# arm.net
KiCad netlist of a schematic drawn in Altium Designer
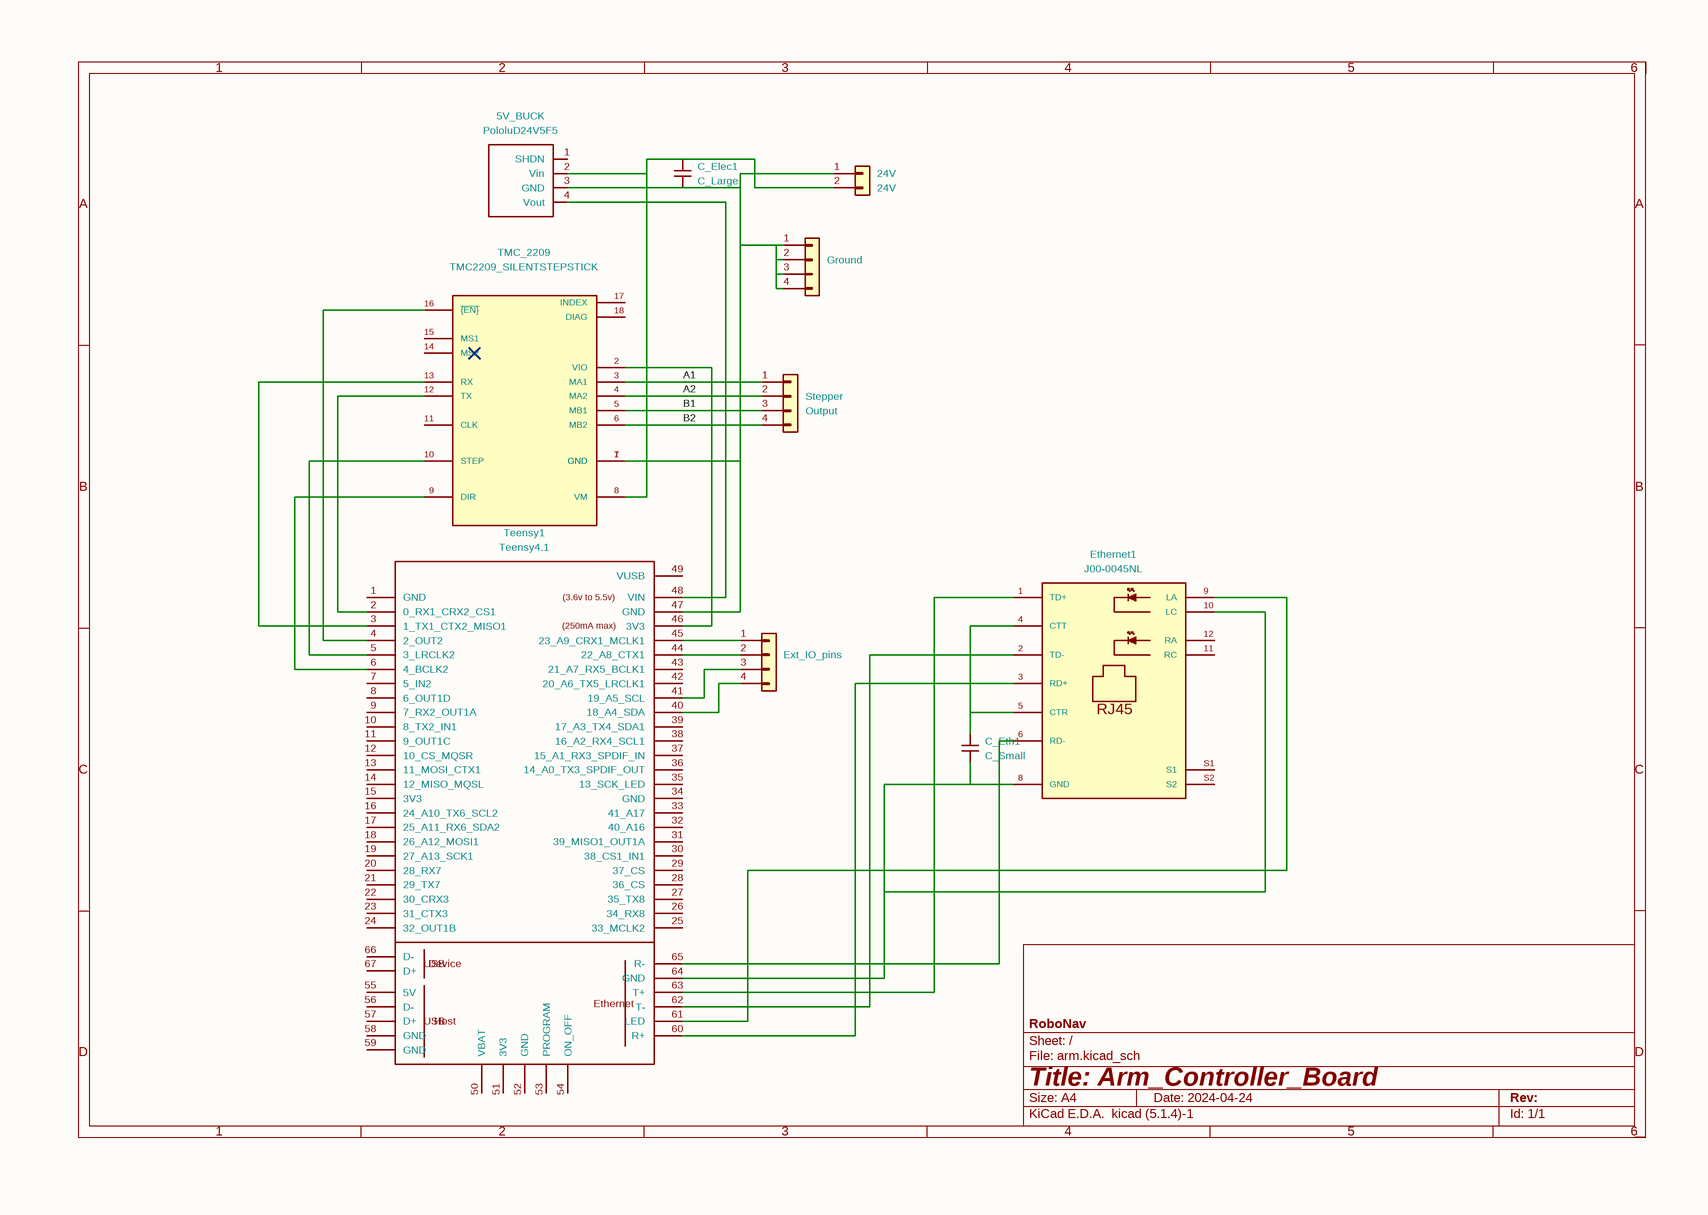
[diagram p0: arm.SchDoc]

(export (version "E")
  (design (tool "Eeschema 10.0.6"))
  (components
    (comp (ref "5V_BUCK") (value "PololuD24V5F5") (libsource (lib "Pololu_5V_D24V5F5") (part "D24V5F5")))
    (comp (ref "24V") (value "24V") (libsource (lib "Connector_Generic") (part "Conn_01x02")))
    (comp (ref "C_Elec1")
      (value "C_Large")
      (description "Unpolarized capacitor, small symbol")
      (libsource (lib "Device") (part "C_Small"))
    )
    (comp (ref "C_Eth1")
      (value "C_Small")
      (description "Unpolarized capacitor, small symbol")
      (libsource (lib "Device") (part "C_Small"))
    )
    (comp (ref "Ethernet1")
      (value "J00-0045NL")
      (description "Conn RJ-45 Integrated Magnetics F 8 POS 2.54mm Solder RA Thru-Hole 12 Terminal 1 Port Cat 5/Cat 6")
      (fields (field (name "MF") "Pulse Electronics"))
      (libsource (lib "EthernetHead") (part "J00-0045NL"))
    )
    (comp (ref "Ext_IO_pins") (value "Output") (libsource (lib "Connector_Generic") (part "Conn_01x04")))
    (comp (ref "Ground") (value "Output") (libsource (lib "Connector_Generic") (part "Conn_01x04")))
    (comp (ref "Stepper") (value "Output") (libsource (lib "Connector_Generic") (part "Conn_01x04")))
    (comp (ref "Teensy1") (value "Teensy4.1") (libsource (lib "Teensy") (part "Teensy4.1")))
    (comp (ref "TMC_2209")
      (value "TMC2209_SILENTSTEPSTICK")
      (libsource (lib "TMC2209_SILENTSTEPSTICK") (part "TMC2209_SILENTSTEPSTICK"))
    )
  )
  (nets
    (net (code "1") (name "/A1") (class "Default")
      (node (ref "Stepper") (pin "1") (pinfunction "Pin_1_1") (pintype "passive"))
      (node (ref "TMC_2209") (pin "3") (pinfunction "MA1_3") (pintype "passive"))
    )
    (net (code "2") (name "/A2") (class "Default")
      (node (ref "Stepper") (pin "2") (pinfunction "Pin_2_2") (pintype "passive"))
      (node (ref "TMC_2209") (pin "4") (pinfunction "MA2_4") (pintype "passive"))
    )
    (net (code "3") (name "/B1") (class "Default")
      (node (ref "Stepper") (pin "3") (pinfunction "Pin_3_3") (pintype "passive"))
      (node (ref "TMC_2209") (pin "5") (pinfunction "MB1_5") (pintype "passive"))
    )
    (net (code "4") (name "/B2") (class "Default")
      (node (ref "Stepper") (pin "4") (pinfunction "Pin_4_4") (pintype "passive"))
      (node (ref "TMC_2209") (pin "6") (pinfunction "MB2_6") (pintype "passive"))
    )
    (net (code "5") (name "Net-(5V_BUCK-Vout)") (class "Default")
      (node (ref "5V_BUCK") (pin "4") (pinfunction "Vout_4") (pintype "passive"))
      (node (ref "Teensy1") (pin "48") (pinfunction "VIN_48") (pintype "passive"))
    )
    (net (code "6") (name "Net-(24V-Pin_1)") (class "Default")
      (node (ref "24V") (pin "1") (pinfunction "Pin_1_1") (pintype "passive"))
      (node (ref "5V_BUCK") (pin "3") (pinfunction "GND_3") (pintype "passive"))
      (node (ref "C_Elec1") (pin "2") (pinfunction "2_2") (pintype "passive"))
      (node (ref "Ground") (pin "1") (pinfunction "Pin_1_1") (pintype "passive"))
      (node (ref "Ground") (pin "2") (pinfunction "Pin_2_2") (pintype "passive"))
      (node (ref "Ground") (pin "3") (pinfunction "Pin_3_3") (pintype "passive"))
      (node (ref "Ground") (pin "4") (pinfunction "Pin_4_4") (pintype "passive"))
      (node (ref "TMC_2209") (pin "1") (pinfunction "GND_1") (pintype "passive"))
      (node (ref "TMC_2209") (pin "7") (pinfunction "GND_7") (pintype "passive"))
      (node (ref "Teensy1") (pin "47") (pinfunction "GND_47") (pintype "passive"))
    )
    (net (code "7") (name "Net-(24V-Pin_2)") (class "Default")
      (node (ref "24V") (pin "2") (pinfunction "Pin_2_2") (pintype "passive"))
      (node (ref "5V_BUCK") (pin "2") (pinfunction "Vin_2") (pintype "passive"))
      (node (ref "C_Elec1") (pin "1") (pinfunction "1_1") (pintype "passive"))
      (node (ref "TMC_2209") (pin "8") (pinfunction "VM_8") (pintype "passive"))
    )
    (net (code "8") (name "Net-(Ethernet1-CTR)") (class "Default")
      (node (ref "C_Eth1") (pin "1") (pinfunction "1_1") (pintype "passive"))
      (node (ref "Ethernet1") (pin "4") (pinfunction "CTT_4") (pintype "passive"))
      (node (ref "Ethernet1") (pin "5") (pinfunction "CTR_5") (pintype "passive"))
    )
    (net (code "9") (name "Net-(Ethernet1-GND)") (class "Default")
      (node (ref "C_Eth1") (pin "2") (pinfunction "2_2") (pintype "passive"))
      (node (ref "Ethernet1") (pin "10") (pinfunction "LC_10") (pintype "passive"))
      (node (ref "Ethernet1") (pin "8") (pinfunction "GND_8") (pintype "passive"))
      (node (ref "Teensy1") (pin "64") (pinfunction "GND_64") (pintype "passive"))
    )
    (net (code "10") (name "Net-(Ethernet1-LA)") (class "Default")
      (node (ref "Ethernet1") (pin "9") (pinfunction "LA_9") (pintype "passive"))
      (node (ref "Teensy1") (pin "61") (pinfunction "LED_61") (pintype "passive"))
    )
    (net (code "11") (name "Net-(Ethernet1-RD+)") (class "Default")
      (node (ref "Ethernet1") (pin "3") (pinfunction "RD+_3") (pintype "passive"))
      (node (ref "Teensy1") (pin "60") (pinfunction "R+_60") (pintype "passive"))
    )
    (net (code "12") (name "Net-(Ethernet1-RD-)") (class "Default")
      (node (ref "Ethernet1") (pin "6") (pinfunction "RD-_6") (pintype "passive"))
      (node (ref "Teensy1") (pin "65") (pinfunction "R-_65") (pintype "passive"))
    )
    (net (code "13") (name "Net-(Ethernet1-TD+)") (class "Default")
      (node (ref "Ethernet1") (pin "1") (pinfunction "TD+_1") (pintype "passive"))
      (node (ref "Teensy1") (pin "63") (pinfunction "T+_63") (pintype "passive"))
    )
    (net (code "14") (name "Net-(Ethernet1-TD-)") (class "Default")
      (node (ref "Ethernet1") (pin "2") (pinfunction "TD-_2") (pintype "passive"))
      (node (ref "Teensy1") (pin "62") (pinfunction "T-_62") (pintype "passive"))
    )
    (net (code "15") (name "Net-(Ext_IO_pins-Pin_1)") (class "Default")
      (node (ref "Ext_IO_pins") (pin "1") (pinfunction "Pin_1_1") (pintype "passive"))
      (node (ref "Teensy1") (pin "45") (pinfunction "23_A9_CRX1_MCLK1_45") (pintype "passive"))
    )
    (net (code "16") (name "Net-(Ext_IO_pins-Pin_2)") (class "Default")
      (node (ref "Ext_IO_pins") (pin "2") (pinfunction "Pin_2_2") (pintype "passive"))
      (node (ref "Teensy1") (pin "44") (pinfunction "22_A8_CTX1_44") (pintype "passive"))
    )
    (net (code "17") (name "Net-(Ext_IO_pins-Pin_3)") (class "Default")
      (node (ref "Ext_IO_pins") (pin "3") (pinfunction "Pin_3_3") (pintype "passive"))
      (node (ref "Teensy1") (pin "41") (pinfunction "19_A5_SCL_41") (pintype "passive"))
    )
    (net (code "18") (name "Net-(Ext_IO_pins-Pin_4)") (class "Default")
      (node (ref "Ext_IO_pins") (pin "4") (pinfunction "Pin_4_4") (pintype "passive"))
      (node (ref "Teensy1") (pin "40") (pinfunction "18_A4_SDA_40") (pintype "passive"))
    )
    (net (code "19") (name "Net-(TMC_2209-DIR)") (class "Default")
      (node (ref "TMC_2209") (pin "9") (pinfunction "DIR_9") (pintype "passive"))
      (node (ref "Teensy1") (pin "6") (pinfunction "4_BCLK2_6") (pintype "passive"))
    )
    (net (code "20") (name "Net-(TMC_2209-RX)") (class "Default")
      (node (ref "TMC_2209") (pin "13") (pinfunction "RX_13") (pintype "passive"))
      (node (ref "Teensy1") (pin "3") (pinfunction "1_TX1_CTX2_MISO1_3") (pintype "passive"))
    )
    (net (code "21") (name "Net-(TMC_2209-STEP)") (class "Default")
      (node (ref "TMC_2209") (pin "10") (pinfunction "STEP_10") (pintype "passive"))
      (node (ref "Teensy1") (pin "5") (pinfunction "3_LRCLK2_5") (pintype "passive"))
    )
    (net (code "22") (name "Net-(TMC_2209-TX)") (class "Default")
      (node (ref "TMC_2209") (pin "12") (pinfunction "TX_12") (pintype "passive"))
      (node (ref "Teensy1") (pin "2") (pinfunction "0_RX1_CRX2_CS1_2") (pintype "passive"))
    )
    (net (code "23") (name "Net-(TMC_2209-VIO)") (class "Default")
      (node (ref "TMC_2209") (pin "2") (pinfunction "VIO_2") (pintype "passive"))
      (node (ref "Teensy1") (pin "46") (pinfunction "3V3_46") (pintype "passive"))
    )
    (net (code "24") (name "Net-(TMC_2209-~{{EN}})") (class "Default")
      (node (ref "TMC_2209") (pin "16") (pinfunction "~{{EN}}_16") (pintype "passive"))
      (node (ref "Teensy1") (pin "4") (pinfunction "2_OUT2_4") (pintype "passive"))
    )
    (net (code "25") (name "unconnected-(5V_BUCK-SHDN-Pad1)") (class "Default")
      (node (ref "5V_BUCK") (pin "1") (pinfunction "SHDN_1") (pintype "passive"))
    )
    (net (code "26") (name "unconnected-(Ethernet1-PadS1)") (class "Default")
      (node (ref "Ethernet1") (pin "S1") (pinfunction "S1_S1") (pintype "passive"))
    )
    (net (code "27") (name "unconnected-(Ethernet1-PadS2)") (class "Default")
      (node (ref "Ethernet1") (pin "S2") (pinfunction "S2_S2") (pintype "passive"))
    )
    (net (code "28") (name "unconnected-(Ethernet1-RA-Pad12)") (class "Default")
      (node (ref "Ethernet1") (pin "12") (pinfunction "RA_12") (pintype "passive"))
    )
    (net (code "29") (name "unconnected-(Ethernet1-RC-Pad11)") (class "Default")
      (node (ref "Ethernet1") (pin "11") (pinfunction "RC_11") (pintype "passive"))
    )
    (net (code "30") (name "unconnected-(TMC_2209-CLK-Pad11)") (class "Default")
      (node (ref "TMC_2209") (pin "11") (pinfunction "CLK_11") (pintype "passive"))
    )
    (net (code "31") (name "unconnected-(TMC_2209-DIAG-Pad18)") (class "Default")
      (node (ref "TMC_2209") (pin "18") (pinfunction "DIAG_18") (pintype "passive"))
    )
    (net (code "32") (name "unconnected-(TMC_2209-INDEX-Pad17)") (class "Default")
      (node (ref "TMC_2209") (pin "17") (pinfunction "INDEX_17") (pintype "passive"))
    )
    (net (code "33") (name "unconnected-(TMC_2209-MS1-Pad15)") (class "Default")
      (node (ref "TMC_2209") (pin "15") (pinfunction "MS1_15") (pintype "passive"))
    )
    (net (code "34") (name "unconnected-(TMC_2209-MS2-Pad14)") (class "Default")
      (node (ref "TMC_2209") (pin "14") (pinfunction "MS2_14") (pintype "passive"))
    )
    (net (code "35") (name "unconnected-(Teensy1-3V3-Pad15)") (class "Default")
      (node (ref "Teensy1") (pin "15") (pinfunction "3V3_15") (pintype "passive"))
    )
    (net (code "36") (name "unconnected-(Teensy1-3V3-Pad51)") (class "Default")
      (node (ref "Teensy1") (pin "51") (pinfunction "3V3_51") (pintype "passive"))
    )
    (net (code "37") (name "unconnected-(Teensy1-5V-Pad55)") (class "Default")
      (node (ref "Teensy1") (pin "55") (pinfunction "5V_55") (pintype "passive"))
    )
    (net (code "38") (name "unconnected-(Teensy1-5_IN2-Pad7)") (class "Default")
      (node (ref "Teensy1") (pin "7") (pinfunction "5_IN2_7") (pintype "passive"))
    )
    (net (code "39") (name "unconnected-(Teensy1-6_OUT1D-Pad8)") (class "Default")
      (node (ref "Teensy1") (pin "8") (pinfunction "6_OUT1D_8") (pintype "passive"))
    )
    (net (code "40") (name "unconnected-(Teensy1-7_RX2_OUT1A-Pad9)") (class "Default")
      (node (ref "Teensy1") (pin "9") (pinfunction "7_RX2_OUT1A_9") (pintype "passive"))
    )
    (net (code "41") (name "unconnected-(Teensy1-8_TX2_IN1-Pad10)") (class "Default")
      (node (ref "Teensy1") (pin "10") (pinfunction "8_TX2_IN1_10") (pintype "passive"))
    )
    (net (code "42") (name "unconnected-(Teensy1-9_OUT1C-Pad11)") (class "Default")
      (node (ref "Teensy1") (pin "11") (pinfunction "9_OUT1C_11") (pintype "passive"))
    )
    (net (code "43") (name "unconnected-(Teensy1-10_CS_MQSR-Pad12)") (class "Default")
      (node (ref "Teensy1") (pin "12") (pinfunction "10_CS_MQSR_12") (pintype "passive"))
    )
    (net (code "44") (name "unconnected-(Teensy1-11_MOSI_CTX1-Pad13)") (class "Default")
      (node (ref "Teensy1") (pin "13") (pinfunction "11_MOSI_CTX1_13") (pintype "passive"))
    )
    (net (code "45") (name "unconnected-(Teensy1-12_MISO_MQSL-Pad14)") (class "Default")
      (node (ref "Teensy1") (pin "14") (pinfunction "12_MISO_MQSL_14") (pintype "passive"))
    )
    (net (code "46") (name "unconnected-(Teensy1-13_SCK_LED-Pad35)") (class "Default")
      (node (ref "Teensy1") (pin "35") (pinfunction "13_SCK_LED_35") (pintype "passive"))
    )
    (net (code "47") (name "unconnected-(Teensy1-14_A0_TX3_SPDIF_OUT-Pad36)") (class "Default")
      (node (ref "Teensy1") (pin "36") (pinfunction "14_A0_TX3_SPDIF_OUT_36") (pintype "passive"))
    )
    (net (code "48") (name "unconnected-(Teensy1-15_A1_RX3_SPDIF_IN-Pad37)") (class "Default")
      (node (ref "Teensy1") (pin "37") (pinfunction "15_A1_RX3_SPDIF_IN_37") (pintype "passive"))
    )
    (net (code "49") (name "unconnected-(Teensy1-16_A2_RX4_SCL1-Pad38)") (class "Default")
      (node (ref "Teensy1") (pin "38") (pinfunction "16_A2_RX4_SCL1_38") (pintype "passive"))
    )
    (net (code "50") (name "unconnected-(Teensy1-17_A3_TX4_SDA1-Pad39)") (class "Default")
      (node (ref "Teensy1") (pin "39") (pinfunction "17_A3_TX4_SDA1_39") (pintype "passive"))
    )
    (net (code "51") (name "unconnected-(Teensy1-20_A6_TX5_LRCLK1-Pad42)") (class "Default")
      (node (ref "Teensy1") (pin "42") (pinfunction "20_A6_TX5_LRCLK1_42") (pintype "passive"))
    )
    (net (code "52") (name "unconnected-(Teensy1-21_A7_RX5_BCLK1-Pad43)") (class "Default")
      (node (ref "Teensy1") (pin "43") (pinfunction "21_A7_RX5_BCLK1_43") (pintype "passive"))
    )
    (net (code "53") (name "unconnected-(Teensy1-24_A10_TX6_SCL2-Pad16)") (class "Default")
      (node (ref "Teensy1") (pin "16") (pinfunction "24_A10_TX6_SCL2_16") (pintype "passive"))
    )
    (net (code "54") (name "unconnected-(Teensy1-25_A11_RX6_SDA2-Pad17)") (class "Default")
      (node (ref "Teensy1") (pin "17") (pinfunction "25_A11_RX6_SDA2_17") (pintype "passive"))
    )
    (net (code "55") (name "unconnected-(Teensy1-26_A12_MOSI1-Pad18)") (class "Default")
      (node (ref "Teensy1") (pin "18") (pinfunction "26_A12_MOSI1_18") (pintype "passive"))
    )
    (net (code "56") (name "unconnected-(Teensy1-27_A13_SCK1-Pad19)") (class "Default")
      (node (ref "Teensy1") (pin "19") (pinfunction "27_A13_SCK1_19") (pintype "passive"))
    )
    (net (code "57") (name "unconnected-(Teensy1-28_RX7-Pad20)") (class "Default")
      (node (ref "Teensy1") (pin "20") (pinfunction "28_RX7_20") (pintype "passive"))
    )
    (net (code "58") (name "unconnected-(Teensy1-29_TX7-Pad21)") (class "Default")
      (node (ref "Teensy1") (pin "21") (pinfunction "29_TX7_21") (pintype "passive"))
    )
    (net (code "59") (name "unconnected-(Teensy1-30_CRX3-Pad22)") (class "Default")
      (node (ref "Teensy1") (pin "22") (pinfunction "30_CRX3_22") (pintype "passive"))
    )
    (net (code "60") (name "unconnected-(Teensy1-31_CTX3-Pad23)") (class "Default")
      (node (ref "Teensy1") (pin "23") (pinfunction "31_CTX3_23") (pintype "passive"))
    )
    (net (code "61") (name "unconnected-(Teensy1-32_OUT1B-Pad24)") (class "Default")
      (node (ref "Teensy1") (pin "24") (pinfunction "32_OUT1B_24") (pintype "passive"))
    )
    (net (code "62") (name "unconnected-(Teensy1-33_MCLK2-Pad25)") (class "Default")
      (node (ref "Teensy1") (pin "25") (pinfunction "33_MCLK2_25") (pintype "passive"))
    )
    (net (code "63") (name "unconnected-(Teensy1-34_RX8-Pad26)") (class "Default")
      (node (ref "Teensy1") (pin "26") (pinfunction "34_RX8_26") (pintype "passive"))
    )
    (net (code "64") (name "unconnected-(Teensy1-35_TX8-Pad27)") (class "Default")
      (node (ref "Teensy1") (pin "27") (pinfunction "35_TX8_27") (pintype "passive"))
    )
    (net (code "65") (name "unconnected-(Teensy1-36_CS-Pad28)") (class "Default")
      (node (ref "Teensy1") (pin "28") (pinfunction "36_CS_28") (pintype "passive"))
    )
    (net (code "66") (name "unconnected-(Teensy1-37_CS-Pad29)") (class "Default")
      (node (ref "Teensy1") (pin "29") (pinfunction "37_CS_29") (pintype "passive"))
    )
    (net (code "67") (name "unconnected-(Teensy1-38_CS1_IN1-Pad30)") (class "Default")
      (node (ref "Teensy1") (pin "30") (pinfunction "38_CS1_IN1_30") (pintype "passive"))
    )
    (net (code "68") (name "unconnected-(Teensy1-39_MISO1_OUT1A-Pad31)") (class "Default")
      (node (ref "Teensy1") (pin "31") (pinfunction "39_MISO1_OUT1A_31") (pintype "passive"))
    )
    (net (code "69") (name "unconnected-(Teensy1-40_A16-Pad32)") (class "Default")
      (node (ref "Teensy1") (pin "32") (pinfunction "40_A16_32") (pintype "passive"))
    )
    (net (code "70") (name "unconnected-(Teensy1-41_A17-Pad33)") (class "Default")
      (node (ref "Teensy1") (pin "33") (pinfunction "41_A17_33") (pintype "passive"))
    )
    (net (code "71") (name "unconnected-(Teensy1-D+-Pad57)") (class "Default")
      (node (ref "Teensy1") (pin "57") (pinfunction "D+_57") (pintype "passive"))
    )
    (net (code "72") (name "unconnected-(Teensy1-D+-Pad67)") (class "Default")
      (node (ref "Teensy1") (pin "67") (pinfunction "D+_67") (pintype "passive"))
    )
    (net (code "73") (name "unconnected-(Teensy1-D--Pad56)") (class "Default")
      (node (ref "Teensy1") (pin "56") (pinfunction "D-_56") (pintype "passive"))
    )
    (net (code "74") (name "unconnected-(Teensy1-D--Pad66)") (class "Default")
      (node (ref "Teensy1") (pin "66") (pinfunction "D-_66") (pintype "passive"))
    )
    (net (code "75") (name "unconnected-(Teensy1-GND-Pad1)") (class "Default")
      (node (ref "Teensy1") (pin "1") (pinfunction "GND_1") (pintype "passive"))
    )
    (net (code "76") (name "unconnected-(Teensy1-GND-Pad34)") (class "Default")
      (node (ref "Teensy1") (pin "34") (pinfunction "GND_34") (pintype "passive"))
    )
    (net (code "77") (name "unconnected-(Teensy1-GND-Pad52)") (class "Default")
      (node (ref "Teensy1") (pin "52") (pinfunction "GND_52") (pintype "passive"))
    )
    (net (code "78") (name "unconnected-(Teensy1-GND-Pad58)") (class "Default")
      (node (ref "Teensy1") (pin "58") (pinfunction "GND_58") (pintype "passive"))
    )
    (net (code "79") (name "unconnected-(Teensy1-GND-Pad59)") (class "Default")
      (node (ref "Teensy1") (pin "59") (pinfunction "GND_59") (pintype "passive"))
    )
    (net (code "80") (name "unconnected-(Teensy1-ON_OFF-Pad54)") (class "Default")
      (node (ref "Teensy1") (pin "54") (pinfunction "ON_OFF_54") (pintype "passive"))
    )
    (net (code "81") (name "unconnected-(Teensy1-PROGRAM-Pad53)") (class "Default")
      (node (ref "Teensy1") (pin "53") (pinfunction "PROGRAM_53") (pintype "passive"))
    )
    (net (code "82") (name "unconnected-(Teensy1-VBAT-Pad50)") (class "Default")
      (node (ref "Teensy1") (pin "50") (pinfunction "VBAT_50") (pintype "passive"))
    )
    (net (code "83") (name "unconnected-(Teensy1-VUSB-Pad49)") (class "Default")
      (node (ref "Teensy1") (pin "49") (pinfunction "VUSB_49") (pintype "passive"))
    )
  )
)
